# Sensing.net
KiCad netlist of a schematic drawn in Altium Designer
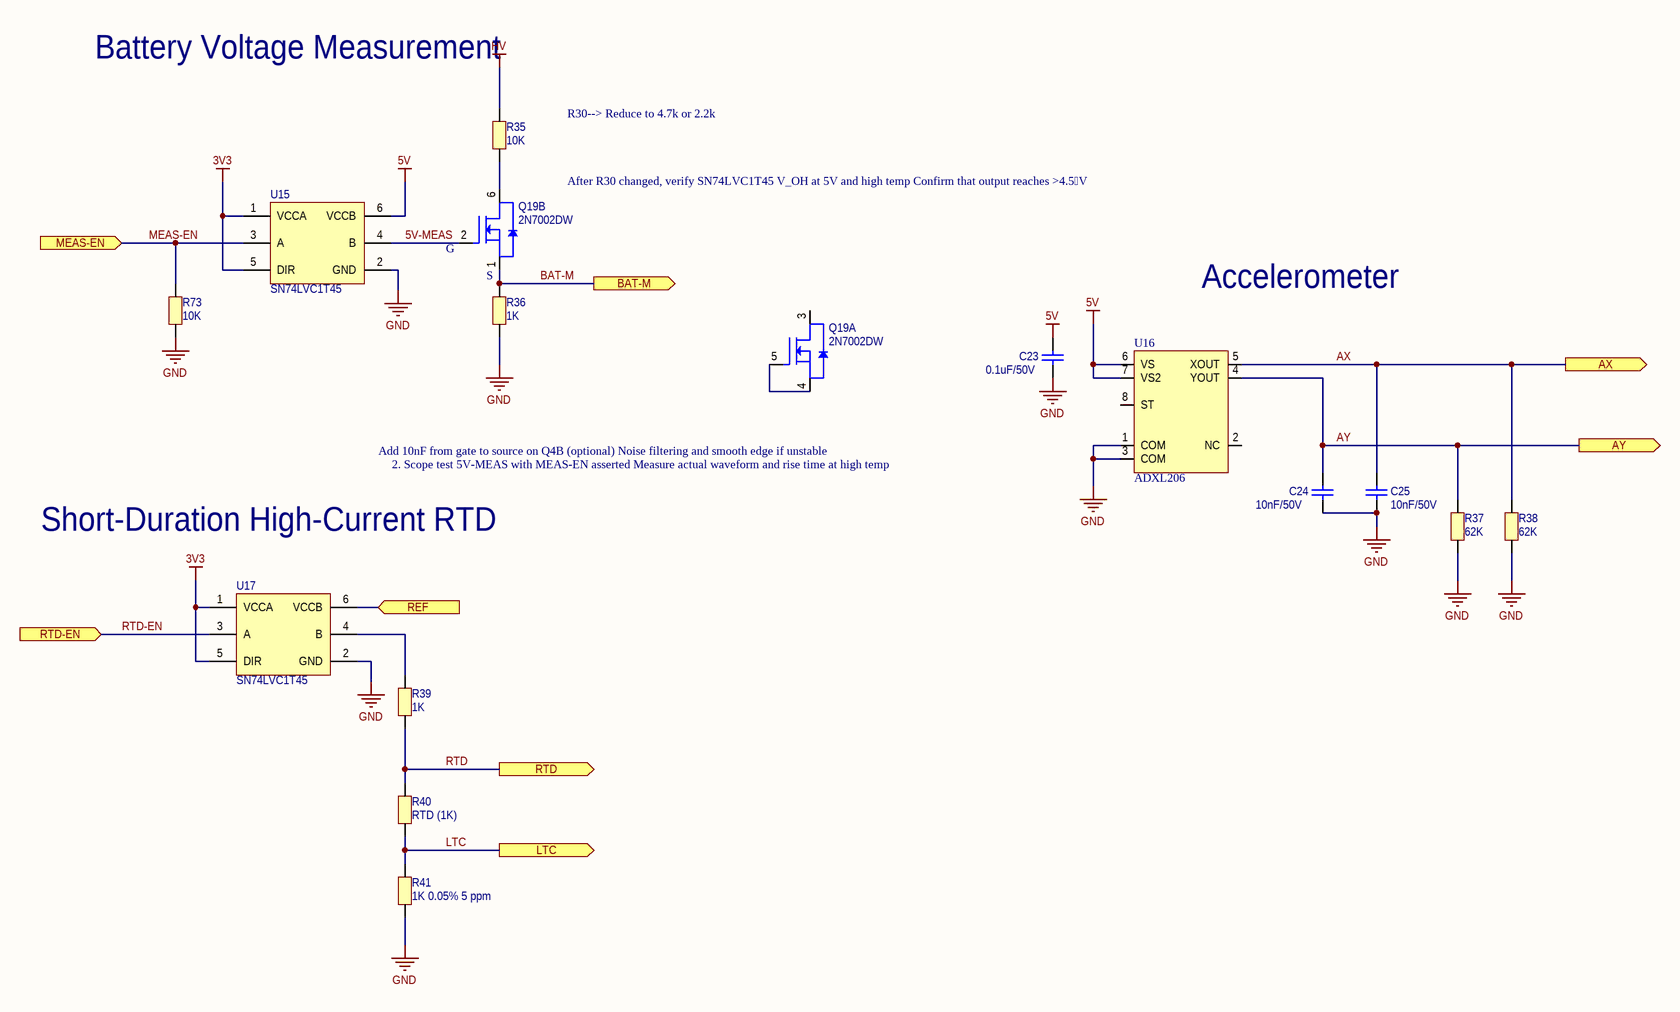
[diagram p0: Sensing.SchDoc]

(export (version "E")
  (design (tool "Eeschema 10.0.6"))
  (components
    (comp (ref "C23")
      (value "0.1uF/50V")
      (footprint "0805-CR")
      (description "Capacitor")
      (fields (field (name "MANUFACTURER") "Murata Electronics North America"))
      (libsource (lib "Miscellaneous Devices") (part "Cap"))
    )
    (comp (ref "C24")
      (value "10nF/50V")
      (footprint "0805-CR")
      (description "Capacitor")
      (fields (field (name "MANUFACTURER") "Murata Electronics North America"))
      (libsource (lib "Miscellaneous Devices") (part "Cap"))
    )
    (comp (ref "C25")
      (value "10nF/50V")
      (footprint "0805-CR")
      (description "Capacitor")
      (fields (field (name "MANUFACTURER") "Murata Electronics North America"))
      (libsource (lib "Miscellaneous Devices") (part "Cap"))
    )
    (comp (ref "Q19")
      (value "2N7002DW")
      (footprint "DCK-6")
      (description "2N7002DW Dual N-Channel FET SC-70-6")
      (fields (field (name "MANUFACTURER") "Fairchild Semiconductor"))
      (libsource (lib "FET") (part "2N7002DW"))
    )
    (comp (ref "R35")
      (value "10K")
      (footprint "0805-CR")
      (description "Resistor")
      (fields (field (name "MANUFACTURER") "Yageo"))
      (libsource (lib "Resistors") (part "RES"))
    )
    (comp (ref "R36")
      (value "1K")
      (footprint "0805-CR")
      (description "Resistor")
      (fields (field (name "MANUFACTURER") "Yageo"))
      (libsource (lib "") (part "RES_1"))
    )
    (comp (ref "R37")
      (value "62K")
      (footprint "0805-CR")
      (description "Resistor")
      (fields (field (name "MANUFACTURER") "Yageo"))
      (libsource (lib "Resistors") (part "RES"))
    )
    (comp (ref "R38")
      (value "62K")
      (footprint "0805-CR")
      (description "Resistor")
      (fields (field (name "MANUFACTURER") "Yageo"))
      (libsource (lib "Resistors") (part "RES"))
    )
    (comp (ref "R39")
      (value "1K")
      (footprint "0805-CR")
      (description "Resistor")
      (fields (field (name "MANUFACTURER") "Yageo"))
      (libsource (lib "") (part "RES_1"))
    )
    (comp (ref "R40")
      (value "RTD (1K)")
      (footprint "F2020")
      (description "Resistor Thermal Device")
      (fields (field (name "MANUFACTURER") "TE Connectivity"))
      (libsource (lib "Resistors") (part "RES"))
    )
    (comp (ref "R41")
      (value "1K 0.05% 5 ppm")
      (footprint "0805-CR")
      (description "Resistor")
      (fields (field (name "MANUFACTURER") "Vishay/Thin Film"))
      (libsource (lib "Resistors") (part "RES"))
    )
    (comp (ref "R73")
      (value "10K")
      (footprint "0805-CR")
      (description "Resistor")
      (fields (field (name "MANUFACTURER") "Yageo"))
      (libsource (lib "") (part "RES_2"))
    )
    (comp (ref "U15")
      (value "SN74LVC1T45")
      (footprint "DBV-6")
      (description "SN74LVC1T45 One Channel Level Shifter/Transceiver")
      (fields (field (name "MANUFACTURER") "Texas Instruments"))
      (libsource (lib "TinyLogic") (part "SN74LVC1T45"))
    )
    (comp (ref "U16")
      (value "ADXL206")
      (footprint "D_8_1_ADI")
      (description "ADXL206 5g High Temperature Accelerometer")
      (fields (field (name "MANUFACTURER") "Analog Devices Inc."))
      (libsource (lib "AD Accelerometers") (part "ADXL206"))
    )
    (comp (ref "U17")
      (value "SN74LVC1T45")
      (footprint "DBV-6")
      (description "SN74LVC1T45 One Channel Level Shifter/Transceiver")
      (fields (field (name "MANUFACTURER") "Texas Instruments"))
      (libsource (lib "TinyLogic") (part "SN74LVC1T45"))
    )
  )
  (nets
    (net (code "1") (name "/5V-MEAS") (class "Default")
      (node (ref "Q19") (pin "2") (pinfunction "G2_2") (pintype "passive"))
      (node (ref "U15") (pin "4") (pinfunction "B_4") (pintype "passive"))
    )
    (net (code "2") (name "/AX") (class "Default")
      (node (ref "C25") (pin "2") (pinfunction "2_2") (pintype "passive"))
      (node (ref "R38") (pin "1") (pinfunction "1_1") (pintype "passive"))
      (node (ref "U16") (pin "5") (pinfunction "XOUT_5") (pintype "passive"))
    )
    (net (code "3") (name "/AY") (class "Default")
      (node (ref "C24") (pin "2") (pinfunction "2_2") (pintype "passive"))
      (node (ref "R37") (pin "1") (pinfunction "1_1") (pintype "passive"))
      (node (ref "U16") (pin "4") (pinfunction "YOUT_4") (pintype "passive"))
    )
    (net (code "4") (name "/BAT-M") (class "Default")
      (node (ref "Q19") (pin "1") (pinfunction "S2_1") (pintype "passive"))
      (node (ref "R36") (pin "2") (pinfunction "2_2") (pintype "passive"))
    )
    (net (code "5") (name "/LTC") (class "Default")
      (node (ref "R40") (pin "2") (pinfunction "2_2") (pintype "passive"))
      (node (ref "R41") (pin "1") (pinfunction "1_1") (pintype "passive"))
    )
    (net (code "6") (name "/MEAS-EN") (class "Default")
      (node (ref "R73") (pin "1") (pinfunction "1_1") (pintype "passive"))
      (node (ref "U15") (pin "3") (pinfunction "A_3") (pintype "passive"))
    )
    (net (code "7") (name "/REF") (class "Default")
      (node (ref "U17") (pin "6") (pinfunction "VCCB_6") (pintype "passive"))
    )
    (net (code "8") (name "/RTD") (class "Default")
      (node (ref "R39") (pin "1") (pinfunction "1_1") (pintype "passive"))
      (node (ref "R40") (pin "1") (pinfunction "1_1") (pintype "passive"))
    )
    (net (code "9") (name "/RTD-EN") (class "Default")
      (node (ref "U17") (pin "3") (pinfunction "A_3") (pintype "passive"))
    )
    (net (code "10") (name "3V3") (class "Default")
      (node (ref "U15") (pin "1") (pinfunction "VCCA_1") (pintype "passive"))
      (node (ref "U15") (pin "5") (pinfunction "DIR_5") (pintype "passive"))
      (node (ref "U17") (pin "1") (pinfunction "VCCA_1") (pintype "passive"))
      (node (ref "U17") (pin "5") (pinfunction "DIR_5") (pintype "passive"))
    )
    (net (code "11") (name "5V") (class "Default")
      (node (ref "C23") (pin "2") (pinfunction "2_2") (pintype "passive"))
      (node (ref "U15") (pin "6") (pinfunction "VCCB_6") (pintype "passive"))
      (node (ref "U16") (pin "6") (pinfunction "VS_6") (pintype "passive"))
      (node (ref "U16") (pin "7") (pinfunction "VS2_7") (pintype "passive"))
    )
    (net (code "12") (name "GND") (class "Default")
      (node (ref "C23") (pin "1") (pinfunction "1_1") (pintype "passive"))
      (node (ref "C24") (pin "1") (pinfunction "1_1") (pintype "passive"))
      (node (ref "C25") (pin "1") (pinfunction "1_1") (pintype "passive"))
      (node (ref "R36") (pin "1") (pinfunction "1_1") (pintype "passive"))
      (node (ref "R37") (pin "2") (pinfunction "2_2") (pintype "passive"))
      (node (ref "R38") (pin "2") (pinfunction "2_2") (pintype "passive"))
      (node (ref "R41") (pin "2") (pinfunction "2_2") (pintype "passive"))
      (node (ref "R73") (pin "2") (pinfunction "2_2") (pintype "passive"))
      (node (ref "U15") (pin "2") (pinfunction "GND_2") (pintype "passive"))
      (node (ref "U16") (pin "1") (pinfunction "COM_1") (pintype "passive"))
      (node (ref "U16") (pin "3") (pinfunction "COM_3") (pintype "passive"))
      (node (ref "U17") (pin "2") (pinfunction "GND_2") (pintype "passive"))
    )
    (net (code "13") (name "HV") (class "Default")
      (node (ref "R35") (pin "1") (pinfunction "1_1") (pintype "passive"))
    )
    (net (code "14") (name "Net-(Q19A-G1)") (class "Default")
      (node (ref "Q19") (pin "4") (pinfunction "S1_4") (pintype "passive"))
      (node (ref "Q19") (pin "5") (pinfunction "G1_5") (pintype "passive"))
    )
    (net (code "15") (name "Net-(Q19B-D2)") (class "Default")
      (node (ref "Q19") (pin "6") (pinfunction "D2_6") (pintype "passive"))
      (node (ref "R35") (pin "2") (pinfunction "2_2") (pintype "passive"))
    )
    (net (code "16") (name "Net-(U17-B)") (class "Default")
      (node (ref "R39") (pin "2") (pinfunction "2_2") (pintype "passive"))
      (node (ref "U17") (pin "4") (pinfunction "B_4") (pintype "passive"))
    )
    (net (code "17") (name "unconnected-(Q19A-D1-Pad3)") (class "Default")
      (node (ref "Q19") (pin "3") (pinfunction "D1_3") (pintype "passive"))
    )
    (net (code "18") (name "unconnected-(U16-NC-Pad2)") (class "Default")
      (node (ref "U16") (pin "2") (pinfunction "NC_2") (pintype "passive"))
    )
    (net (code "19") (name "unconnected-(U16-ST-Pad8)") (class "Default")
      (node (ref "U16") (pin "8") (pinfunction "ST_8") (pintype "passive"))
    )
  )
)
